# 12V-3V3_Divider.net
KiCad netlist of a schematic drawn in Altium Designer
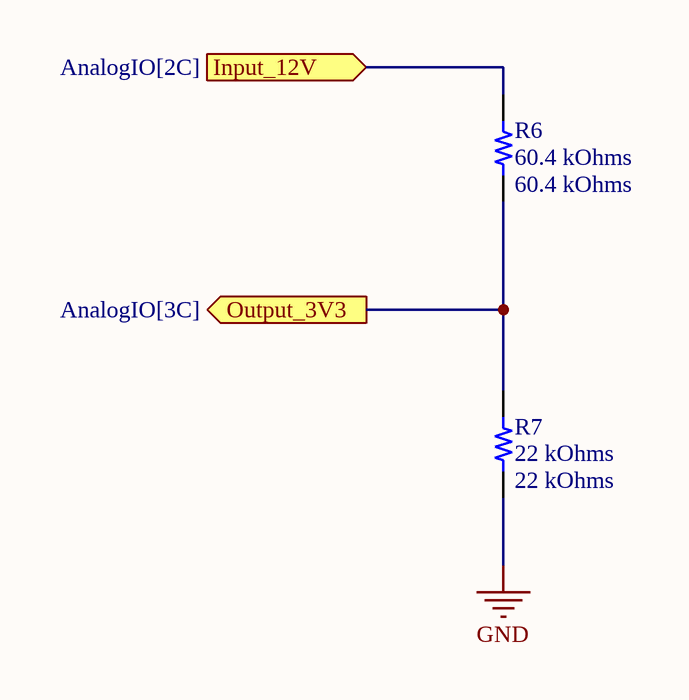
[diagram p0: 12V-3V3_Divider.SchDoc]

(export (version "E")
  (design (tool "Eeschema 10.0.6"))
  (components
    (comp (ref "R6")
      (value "60.4 kOhms")
      (footprint "RES 0603_1608")
      (description "RES SMD 60.4K OHM 1% 1/10W 0603")
      (fields (field (name "PART NUMBER") "AC0603FR-0760K4L") (field (name "ALTIUM_VALUE") "60.4 kOhms"))
      (libsource (lib "altium_library") (part "Resistor"))
    )
    (comp (ref "R7")
      (value "22 kOhms")
      (footprint "RES 0603_1608")
      (description "RES 22K OHM 1% 1/5W 0603")
      (fields (field (name "PART NUMBER") "AC0603FR-7W22KL") (field (name "ALTIUM_VALUE") "22 kOhms"))
      (libsource (lib "altium_library") (part "Resistor"))
    )
  )
  (nets
    (net (code "1") (name "/Input_12V") (class "Default")
      (node (ref "R6") (pin "2") (pinfunction "2_2") (pintype "passive"))
    )
    (net (code "2") (name "/Output_3V3") (class "Default")
      (node (ref "R6") (pin "1") (pinfunction "1_1") (pintype "passive"))
      (node (ref "R7") (pin "2") (pinfunction "2_2") (pintype "passive"))
    )
    (net (code "3") (name "GND") (class "Default")
      (node (ref "R7") (pin "1") (pinfunction "1_1") (pintype "passive"))
    )
  )
)
